# Resonant_Filter.net
KiCad netlist of a schematic drawn in EAGLE
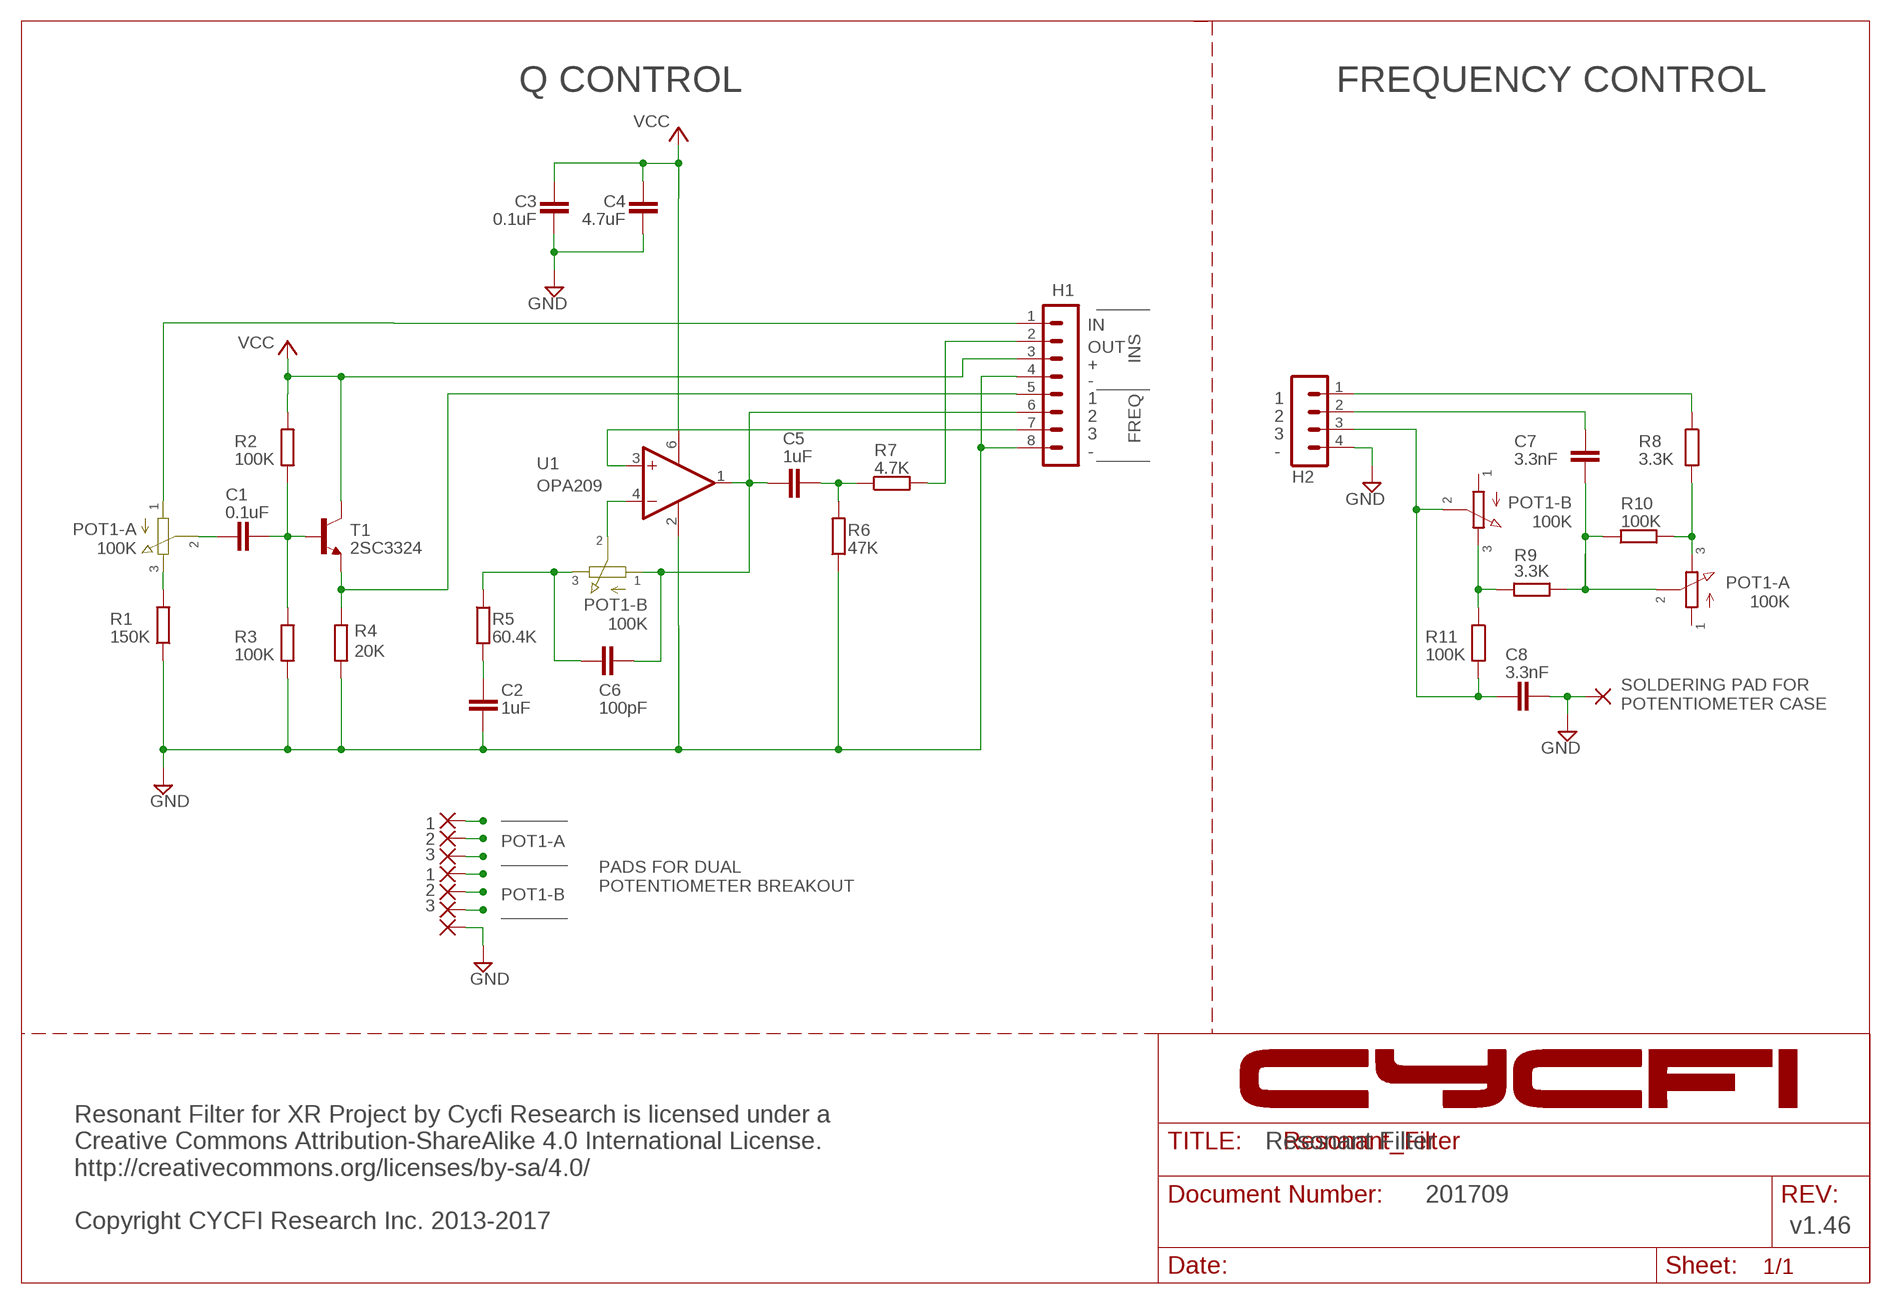
[diagram p0: schematic, sheet 1]

(export (version "E")
  (design (tool "Eeschema 10.0.6"))
  (components
    (comp (ref "C1")
      (value "0.1uF")
      (footprint "eagle-import:C0603")
      (libsource (lib "eagle-import") (part "C-EUC0603"))
    )
    (comp (ref "C2")
      (value "1uF")
      (footprint "eagle-import:C0805")
      (libsource (lib "eagle-import") (part "C-EUC0805"))
    )
    (comp (ref "C3")
      (value "0.1uF")
      (footprint "eagle-import:C0603")
      (libsource (lib "eagle-import") (part "C-EUC0603"))
    )
    (comp (ref "C4")
      (value "4.7uF")
      (footprint "eagle-import:C0603")
      (libsource (lib "eagle-import") (part "C-EUC0603"))
    )
    (comp (ref "C5")
      (value "1uF")
      (footprint "eagle-import:C0805")
      (libsource (lib "eagle-import") (part "C-EUC0805"))
    )
    (comp (ref "C6")
      (value "100pF")
      (footprint "eagle-import:C0805")
      (libsource (lib "eagle-import") (part "C-EUC0805"))
    )
    (comp (ref "C7")
      (value "3.3nF")
      (footprint "eagle-import:C0805")
      (libsource (lib "eagle-import") (part "C-EUC0805"))
    )
    (comp (ref "C8")
      (value "3.3nF")
      (footprint "eagle-import:C0805")
      (libsource (lib "eagle-import") (part "C-EUC0805"))
    )
    (comp (ref "H1")
      (value "MA08-1")
      (footprint "eagle-import:MA08-1")
      (libsource (lib "eagle-import") (part "MA08-1"))
    )
    (comp (ref "H2")
      (value "MA04-1")
      (footprint "eagle-import:MA04-1")
      (libsource (lib "eagle-import") (part "MA04-1"))
    )
    (comp (ref "PAD1")
      (value "SMD2")
      (footprint "eagle-import:SMD1,27-2,54")
      (libsource (lib "eagle-import") (part "SMD2"))
    )
    (comp (ref "PAD2")
      (value "SMD2")
      (footprint "eagle-import:SMD1,27-2,54")
      (libsource (lib "eagle-import") (part "SMD2"))
    )
    (comp (ref "PAD3")
      (value "SMD2")
      (footprint "eagle-import:SMD1,27-2,54")
      (libsource (lib "eagle-import") (part "SMD2"))
    )
    (comp (ref "PAD4")
      (value "SMD2")
      (footprint "eagle-import:SMD1,27-2,54")
      (libsource (lib "eagle-import") (part "SMD2"))
    )
    (comp (ref "PAD5")
      (value "SMD2")
      (footprint "eagle-import:SMD1,27-2,54")
      (libsource (lib "eagle-import") (part "SMD2"))
    )
    (comp (ref "PAD6")
      (value "SMD2")
      (footprint "eagle-import:SMD1,27-2,54")
      (libsource (lib "eagle-import") (part "SMD2"))
    )
    (comp (ref "PAD7")
      (value "SMD2")
      (footprint "eagle-import:SMD1,27-2,54")
      (libsource (lib "eagle-import") (part "SMD2"))
    )
    (comp (ref "PAD8")
      (value "1,6/0,9")
      (footprint "eagle-import:1,6_0,9")
      (libsource (lib "eagle-import") (part "1,6/0,9"))
    )
    (comp (ref "POT1-A")
      (value "PDB182-GTR02")
      (footprint "eagle-import:PDB182-GTR01")
      (libsource (lib "eagle-import") (part "PDB182-GTR02"))
    )
    (comp (ref "R1")
      (value "150K")
      (footprint "eagle-import:R0402")
      (libsource (lib "eagle-import") (part "R-EU_R0402"))
    )
    (comp (ref "R2")
      (value "100K")
      (footprint "eagle-import:R0402")
      (libsource (lib "eagle-import") (part "R-EU_R0402"))
    )
    (comp (ref "R3")
      (value "100K")
      (footprint "eagle-import:R0402")
      (libsource (lib "eagle-import") (part "R-EU_R0402"))
    )
    (comp (ref "R4")
      (value "20K")
      (footprint "eagle-import:R0402")
      (libsource (lib "eagle-import") (part "R-EU_R0402"))
    )
    (comp (ref "R5")
      (value "60.4K")
      (footprint "eagle-import:R0402")
      (libsource (lib "eagle-import") (part "R-EU_R0402"))
    )
    (comp (ref "R6")
      (value "47K")
      (footprint "eagle-import:R0402")
      (libsource (lib "eagle-import") (part "R-EU_R0402"))
    )
    (comp (ref "R7")
      (value "4.7K")
      (footprint "eagle-import:R0402")
      (libsource (lib "eagle-import") (part "R-EU_R0402"))
    )
    (comp (ref "R8")
      (value "3.3K")
      (footprint "eagle-import:R0603")
      (libsource (lib "eagle-import") (part "R-EU_R0603"))
    )
    (comp (ref "R9")
      (value "3.3K")
      (footprint "eagle-import:R0603")
      (libsource (lib "eagle-import") (part "R-EU_R0603"))
    )
    (comp (ref "R10")
      (value "100K")
      (footprint "eagle-import:R0402")
      (libsource (lib "eagle-import") (part "R-EU_R0402"))
    )
    (comp (ref "R11")
      (value "100K")
      (footprint "eagle-import:R0402")
      (libsource (lib "eagle-import") (part "R-EU_R0402"))
    )
    (comp (ref "T1")
      (value "2SC3324")
      (footprint "eagle-import:SOT23")
      (libsource (lib "eagle-import") (part "BC846"))
    )
    (comp (ref "U1")
      (value "OPA209")
      (footprint "eagle-import:SOT23-6")
      (libsource (lib "eagle-import") (part "OPA836"))
    )
  )
  (nets
    (net (code "1") (name "/BYP") (class "Default")
      (node (ref "H1") (pin "1") (pinfunction "1_1") (pintype "passive"))
      (node (ref "PAD1") (pin "1") (pinfunction "P_1") (pintype "passive"))
    )
    (net (code "2") (name "/INPUT") (class "Default")
      (node (ref "C1") (pin "1") (pinfunction "1_1") (pintype "passive"))
      (node (ref "PAD2") (pin "1") (pinfunction "P_1") (pintype "passive"))
    )
    (net (code "3") (name "/PA-3") (class "Default")
      (node (ref "PAD3") (pin "1") (pinfunction "P_1") (pintype "passive"))
      (node (ref "R1") (pin "2") (pinfunction "2_2") (pintype "passive"))
    )
    (net (code "4") (name "/PTB-1") (class "Default")
      (node (ref "C5") (pin "2") (pinfunction "2_2") (pintype "passive"))
      (node (ref "C6") (pin "2") (pinfunction "2_2") (pintype "passive"))
      (node (ref "H1") (pin "6") (pinfunction "6_6") (pintype "passive"))
      (node (ref "PAD5") (pin "1") (pinfunction "P_1") (pintype "passive"))
      (node (ref "U1") (pin "1") (pinfunction "OUT_1") (pintype "output"))
    )
    (net (code "5") (name "/PTB-2") (class "Default")
      (node (ref "PAD6") (pin "1") (pinfunction "P_1") (pintype "passive"))
      (node (ref "U1") (pin "4") (pinfunction "-IN_4") (pintype "input"))
    )
    (net (code "6") (name "/PTB-3") (class "Default")
      (node (ref "C6") (pin "1") (pinfunction "1_1") (pintype "passive"))
      (node (ref "PAD4") (pin "1") (pinfunction "P_1") (pintype "passive"))
      (node (ref "R5") (pin "1") (pinfunction "1_1") (pintype "passive"))
    )
    (net (code "7") (name "GND") (class "Default")
      (node (ref "C2") (pin "1") (pinfunction "1_1") (pintype "passive"))
      (node (ref "C3") (pin "1") (pinfunction "1_1") (pintype "passive"))
      (node (ref "C4") (pin "1") (pinfunction "1_1") (pintype "passive"))
      (node (ref "C8") (pin "2") (pinfunction "2_2") (pintype "passive"))
      (node (ref "H1") (pin "4") (pinfunction "4_4") (pintype "passive"))
      (node (ref "H1") (pin "8") (pinfunction "8_8") (pintype "passive"))
      (node (ref "H2") (pin "4") (pinfunction "4_4") (pintype "passive"))
      (node (ref "PAD7") (pin "1") (pinfunction "P_1") (pintype "passive"))
      (node (ref "PAD8") (pin "1") (pinfunction "P_1") (pintype "passive"))
      (node (ref "R1") (pin "1") (pinfunction "1_1") (pintype "passive"))
      (node (ref "R3") (pin "1") (pinfunction "1_1") (pintype "passive"))
      (node (ref "R4") (pin "1") (pinfunction "1_1") (pintype "passive"))
      (node (ref "R6") (pin "1") (pinfunction "1_1") (pintype "passive"))
      (node (ref "U1") (pin "2") (pinfunction "V-_2") (pintype "power_in"))
    )
    (net (code "8") (name "Net-(C2-Pad2)") (class "Default")
      (node (ref "C2") (pin "2") (pinfunction "2_2") (pintype "passive"))
      (node (ref "R5") (pin "2") (pinfunction "2_2") (pintype "passive"))
    )
    (net (code "9") (name "Net-(C5-Pad1)") (class "Default")
      (node (ref "C5") (pin "1") (pinfunction "1_1") (pintype "passive"))
      (node (ref "R6") (pin "2") (pinfunction "2_2") (pintype "passive"))
      (node (ref "R7") (pin "1") (pinfunction "1_1") (pintype "passive"))
    )
    (net (code "10") (name "Net-(C7-Pad2)") (class "Default")
      (node (ref "C7") (pin "2") (pinfunction "2_2") (pintype "passive"))
      (node (ref "H2") (pin "2") (pinfunction "2_2") (pintype "passive"))
    )
    (net (code "11") (name "Net-(H1-Pad2)") (class "Default")
      (node (ref "H1") (pin "2") (pinfunction "2_2") (pintype "passive"))
      (node (ref "R7") (pin "2") (pinfunction "2_2") (pintype "passive"))
    )
    (net (code "12") (name "Net-(H2-Pad1)") (class "Default")
      (node (ref "H2") (pin "1") (pinfunction "1_1") (pintype "passive"))
      (node (ref "R8") (pin "1") (pinfunction "1_1") (pintype "passive"))
    )
    (net (code "13") (name "Net-(POT1-AA-2)") (class "Default")
      (node (ref "C7") (pin "1") (pinfunction "1_1") (pintype "passive"))
      (node (ref "POT1-A") (pin "A2") (pinfunction "2_A2") (pintype "passive"))
      (node (ref "R10") (pin "1") (pinfunction "1_1") (pintype "passive"))
      (node (ref "R9") (pin "1") (pinfunction "1_1") (pintype "passive"))
    )
    (net (code "14") (name "Net-(POT1-AA-3)") (class "Default")
      (node (ref "POT1-A") (pin "A3") (pinfunction "3_A3") (pintype "passive"))
      (node (ref "R10") (pin "2") (pinfunction "2_2") (pintype "passive"))
      (node (ref "R8") (pin "2") (pinfunction "2_2") (pintype "passive"))
    )
    (net (code "15") (name "Net-(POT1-AB-2)") (class "Default")
      (node (ref "C8") (pin "1") (pinfunction "1_1") (pintype "passive"))
      (node (ref "H2") (pin "3") (pinfunction "3_3") (pintype "passive"))
      (node (ref "POT1-A") (pin "B2") (pinfunction "2_B2") (pintype "passive"))
      (node (ref "R11") (pin "2") (pinfunction "2_2") (pintype "passive"))
    )
    (net (code "16") (name "Net-(POT1-AB-3)") (class "Default")
      (node (ref "POT1-A") (pin "B3") (pinfunction "3_B3") (pintype "passive"))
      (node (ref "R11") (pin "1") (pinfunction "1_1") (pintype "passive"))
      (node (ref "R9") (pin "2") (pinfunction "2_2") (pintype "passive"))
    )
    (net (code "17") (name "Net-(T1-B)") (class "Default")
      (node (ref "C1") (pin "2") (pinfunction "2_2") (pintype "passive"))
      (node (ref "R2") (pin "1") (pinfunction "1_1") (pintype "passive"))
      (node (ref "R3") (pin "2") (pinfunction "2_2") (pintype "passive"))
      (node (ref "T1") (pin "1") (pinfunction "B_1") (pintype "passive"))
    )
    (net (code "18") (name "Net-(T1-E)") (class "Default")
      (node (ref "H1") (pin "5") (pinfunction "5_5") (pintype "passive"))
      (node (ref "R4") (pin "2") (pinfunction "2_2") (pintype "passive"))
      (node (ref "T1") (pin "2") (pinfunction "E_2") (pintype "passive"))
    )
    (net (code "19") (name "Net-(U1-+IN)") (class "Default")
      (node (ref "H1") (pin "7") (pinfunction "7_7") (pintype "passive"))
      (node (ref "U1") (pin "3") (pinfunction "+IN_3") (pintype "input"))
    )
    (net (code "20") (name "VCC") (class "Default")
      (node (ref "C3") (pin "2") (pinfunction "2_2") (pintype "passive"))
      (node (ref "C4") (pin "2") (pinfunction "2_2") (pintype "passive"))
      (node (ref "H1") (pin "3") (pinfunction "3_3") (pintype "passive"))
      (node (ref "R2") (pin "2") (pinfunction "2_2") (pintype "passive"))
      (node (ref "T1") (pin "3") (pinfunction "C_3") (pintype "passive"))
      (node (ref "U1") (pin "6") (pinfunction "V+_6") (pintype "power_in"))
    )
    (net (code "21") (name "unconnected-(POT1-AA-1-PadA1)") (class "Default")
      (node (ref "POT1-A") (pin "A1") (pinfunction "1_A1") (pintype "passive"))
    )
    (net (code "22") (name "unconnected-(POT1-AB-1-PadB1)") (class "Default")
      (node (ref "POT1-A") (pin "B1") (pinfunction "1_B1") (pintype "passive"))
    )
  )
)
